# 7___Buzzer.net
KiCad netlist of a schematic drawn in Altium Designer
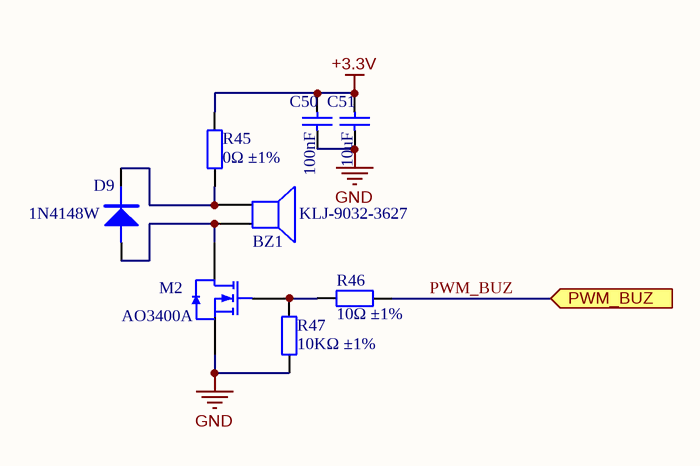
[diagram p0: 7_电子天平_Buzzer.SchDoc]

(export (version "E")
  (design (tool "Eeschema 10.0.6"))
  (components
    (comp (ref "BZ1")
      (value "KLJ-9032-3627")
      (footprint "BUZZER_SMD1")
      (description "额定电压3.6V  谐振频率2731Hz  线圈电阻16Ω")
      (fields (field (name "PUBLISHER") "Altium Limited"))
      (libsource (lib "Miscellaneous Devices") (part "Speaker"))
    )
    (comp (ref "C50")
      (value "100nF")
      (footprint "LC-0805_C")
      (description "MLCC")
      (fields (field (name "PUBLISHER") "Altium Limited"))
      (libsource (lib "Miscellaneous Devices") (part "Cap"))
    )
    (comp (ref "C51")
      (value "10uF")
      (footprint "LC-1206_C")
      (description "MLCC")
      (fields (field (name "PUBLISHER") "Altium Limited"))
      (libsource (lib "Miscellaneous Devices") (part "Cap"))
    )
    (comp (ref "D9")
      (value "1N4148W")
      (footprint "LC-SOD-123")
      (description "100V，150mA，VF=1.25V@150mA")
      (libsource (lib "altium-import") (part "root_1_DIODE_"))
    )
    (comp (ref "M2")
      (value "AO3400A")
      (footprint "LC-SOT-23(SOT-23-3)")
      (description "MOS(场效应管)")
      (libsource (lib "Miscellaneous Devices LC") (part "AO3400A N道沟 X0YV1T SOT-23"))
    )
    (comp (ref "R45")
      (value "0Ω ±1%")
      (footprint "LC-0805_R")
      (description "Resistor")
      (fields (field (name "PUBLISHER") "Altium Limited"))
      (libsource (lib "Miscellaneous Devices") (part "Res2"))
    )
    (comp (ref "R46")
      (value "10Ω ±1%")
      (footprint "LC-0805_R")
      (description "Resistor")
      (fields (field (name "PUBLISHER") "Altium Limited"))
      (libsource (lib "") (part "Res2_1"))
    )
    (comp (ref "R47")
      (value "10KΩ ±1%")
      (footprint "LC-0805_R")
      (description "Resistor")
      (fields (field (name "PUBLISHER") "Altium Limited"))
      (libsource (lib "") (part "Res2_2"))
    )
  )
  (nets
    (net (code "1") (name "+3.3V") (class "Default")
      (node (ref "C50") (pin "1") (pinfunction "1_1") (pintype "passive"))
      (node (ref "C51") (pin "1") (pinfunction "1_1") (pintype "passive"))
      (node (ref "R45") (pin "2") (pinfunction "2_2") (pintype "passive"))
    )
    (net (code "2") (name "/PWM_BUZ") (class "Default")
      (node (ref "R46") (pin "2") (pinfunction "2_2") (pintype "passive"))
    )
    (net (code "3") (name "GND") (class "Default")
      (node (ref "C50") (pin "2") (pinfunction "2_2") (pintype "passive"))
      (node (ref "C51") (pin "2") (pinfunction "2_2") (pintype "passive"))
      (node (ref "M2") (pin "2") (pinfunction "S_2") (pintype "passive"))
      (node (ref "R47") (pin "2") (pinfunction "2_2") (pintype "passive"))
    )
    (net (code "4") (name "Net-(BZ1-Pad1)") (class "Default")
      (node (ref "BZ1") (pin "1") (pinfunction "1_1") (pintype "passive"))
      (node (ref "D9") (pin "K") (pintype "passive"))
      (node (ref "R45") (pin "1") (pinfunction "1_1") (pintype "passive"))
    )
    (net (code "5") (name "Net-(M2-D)") (class "Default")
      (node (ref "BZ1") (pin "2") (pinfunction "2_2") (pintype "passive"))
      (node (ref "D9") (pin "A") (pintype "passive"))
      (node (ref "M2") (pin "3") (pinfunction "D_3") (pintype "passive"))
    )
    (net (code "6") (name "Net-(M2-G)") (class "Default")
      (node (ref "M2") (pin "1") (pinfunction "G_1") (pintype "passive"))
      (node (ref "R46") (pin "1") (pinfunction "1_1") (pintype "passive"))
      (node (ref "R47") (pin "1") (pinfunction "1_1") (pintype "passive"))
    )
  )
)
